# Communications_Board_-_Top.net
KiCad netlist of a schematic drawn in EAGLE
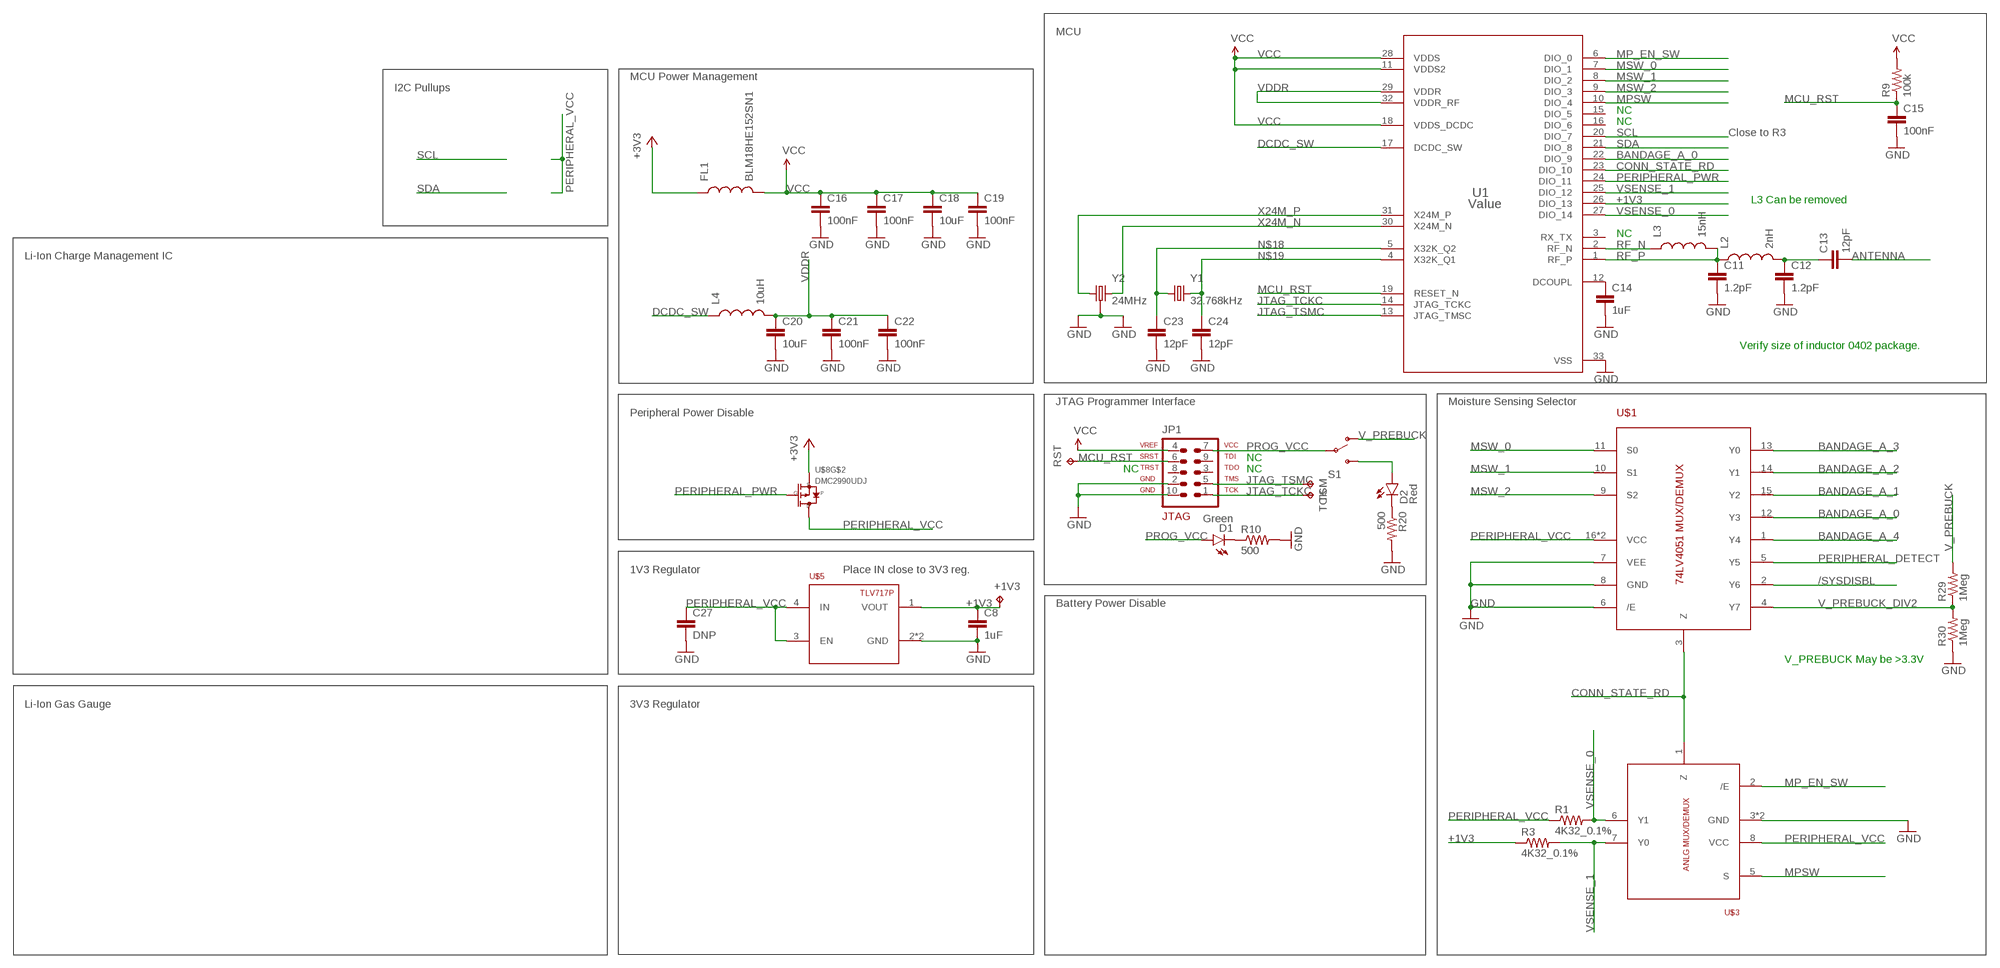
[diagram p0: schematic, sheet 1]
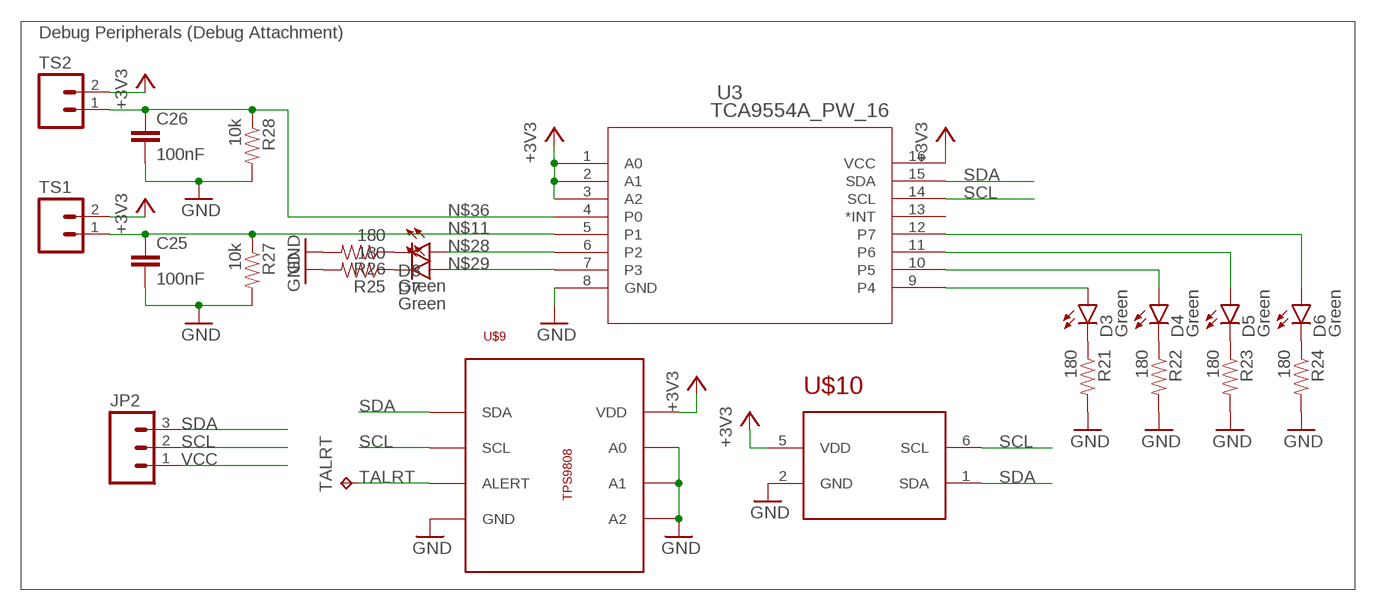
[diagram p1: schematic, sheet 2]
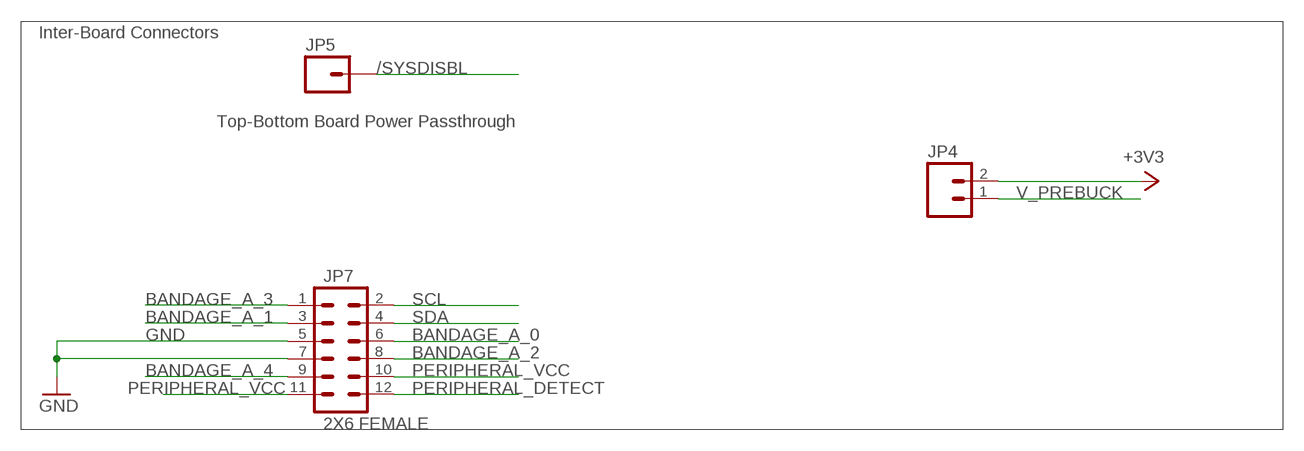
[diagram p2: schematic, sheet 3]

(export (version "E")
  (design (tool "Eeschema 10.0.6"))
  (components
    (comp (ref "+1V3")
      (value "TPTP10R")
      (footprint "eagle-import:TP10R")
      (libsource (lib "eagle-import") (part "TPTP10R"))
    )
    (comp (ref "C8")
      (value "1uF")
      (footprint "eagle-import:0402-CAP")
      (libsource (lib "eagle-import") (part "CAP0402-CAP"))
    )
    (comp (ref "C11")
      (value "1.2pF")
      (footprint "eagle-import:0402-CAP")
      (libsource (lib "eagle-import") (part "CAP0402-CAP"))
    )
    (comp (ref "C12")
      (value "1.2pF")
      (footprint "eagle-import:0402-CAP")
      (libsource (lib "eagle-import") (part "CAP0402-CAP"))
    )
    (comp (ref "C13")
      (value "12pF")
      (footprint "eagle-import:0402-CAP")
      (libsource (lib "eagle-import") (part "CAP0402-CAP"))
    )
    (comp (ref "C14")
      (value "1uF")
      (footprint "eagle-import:0402-CAP")
      (libsource (lib "eagle-import") (part "CAP0402-CAP"))
    )
    (comp (ref "C15")
      (value "100nF")
      (footprint "eagle-import:0402-CAP")
      (libsource (lib "eagle-import") (part "CAP0402-CAP"))
    )
    (comp (ref "C16")
      (value "100nF")
      (footprint "eagle-import:0402-CAP")
      (libsource (lib "eagle-import") (part "CAP0402-CAP"))
    )
    (comp (ref "C17")
      (value "100nF")
      (footprint "eagle-import:0402-CAP")
      (libsource (lib "eagle-import") (part "CAP0402-CAP"))
    )
    (comp (ref "C18")
      (value "10uF")
      (footprint "eagle-import:0402-CAP")
      (libsource (lib "eagle-import") (part "CAP0402-CAP"))
    )
    (comp (ref "C19")
      (value "100nF")
      (footprint "eagle-import:0402-CAP")
      (libsource (lib "eagle-import") (part "CAP0402-CAP"))
    )
    (comp (ref "C20")
      (value "10uF")
      (footprint "eagle-import:0402-CAP")
      (libsource (lib "eagle-import") (part "CAP0402-CAP"))
    )
    (comp (ref "C21")
      (value "100nF")
      (footprint "eagle-import:0402-CAP")
      (libsource (lib "eagle-import") (part "CAP0402-CAP"))
    )
    (comp (ref "C22")
      (value "100nF")
      (footprint "eagle-import:0402-CAP")
      (libsource (lib "eagle-import") (part "CAP0402-CAP"))
    )
    (comp (ref "C23")
      (value "12pF")
      (footprint "eagle-import:0402-CAP")
      (libsource (lib "eagle-import") (part "CAP0402-CAP"))
    )
    (comp (ref "C24")
      (value "12pF")
      (footprint "eagle-import:0402-CAP")
      (libsource (lib "eagle-import") (part "CAP0402-CAP"))
    )
    (comp (ref "C27")
      (value "DNP")
      (footprint "eagle-import:0402-CAP")
      (libsource (lib "eagle-import") (part "CAP0402-CAP"))
    )
    (comp (ref "D1")
      (value "Green")
      (footprint "eagle-import:LED-1206")
      (libsource (lib "eagle-import") (part "LED1206"))
    )
    (comp (ref "D2")
      (value "Red")
      (footprint "eagle-import:LED-1206")
      (libsource (lib "eagle-import") (part "LED1206"))
    )
    (comp (ref "FL1")
      (value "BLM18HE152SN1")
      (footprint "eagle-import:0603")
      (libsource (lib "eagle-import") (part "INDUCTOR0603"))
    )
    (comp (ref "JP1")
      (value "AVR-JTAG-10")
      (footprint "eagle-import:AVR-JTAG-10")
      (libsource (lib "eagle-import") (part "AVR-JTAG-10"))
    )
    (comp (ref "L2")
      (value "2nH")
      (footprint "eagle-import:C0402")
      (libsource (lib "eagle-import") (part "SparkFun-Passives_INDUCTOR0402"))
    )
    (comp (ref "L3")
      (value "15nH")
      (footprint "eagle-import:C0402")
      (libsource (lib "eagle-import") (part "SparkFun-Passives_INDUCTOR0402"))
    )
    (comp (ref "L4")
      (value "10uH")
      (footprint "eagle-import:0603")
      (libsource (lib "eagle-import") (part "INDUCTOR0603"))
    )
    (comp (ref "R1")
      (value "4K32_0.1%")
      (footprint "eagle-import:0402-RES")
      (libsource (lib "eagle-import") (part "RESISTOR0402-RES"))
    )
    (comp (ref "R3")
      (value "4K32_0.1%")
      (footprint "eagle-import:0402-RES")
      (libsource (lib "eagle-import") (part "RESISTOR0402-RES"))
    )
    (comp (ref "R9")
      (value "100k")
      (footprint "eagle-import:0603-RES")
      (libsource (lib "eagle-import") (part "RESISTOR0603-RES"))
    )
    (comp (ref "R10")
      (value "500")
      (footprint "eagle-import:0603-RES")
      (libsource (lib "eagle-import") (part "RESISTOR0603-RES"))
    )
    (comp (ref "R20")
      (value "500")
      (footprint "eagle-import:0603-RES")
      (libsource (lib "eagle-import") (part "RESISTOR0603-RES"))
    )
    (comp (ref "R29")
      (value "1Meg")
      (footprint "eagle-import:0402-RES")
      (libsource (lib "eagle-import") (part "RESISTOR0402-RES"))
    )
    (comp (ref "R30")
      (value "1Meg")
      (footprint "eagle-import:0402-RES")
      (libsource (lib "eagle-import") (part "RESISTOR0402-RES"))
    )
    (comp (ref "RST")
      (value "TPTP10R")
      (footprint "eagle-import:TP10R")
      (libsource (lib "eagle-import") (part "TPTP10R"))
    )
    (comp (ref "S1")
      (value "SWITCH-SPDT")
      (footprint "eagle-import:JS102011SAQN")
      (libsource (lib "eagle-import") (part "SWITCH-SPDT"))
    )
    (comp (ref "TCK")
      (value "TPTP10R")
      (footprint "eagle-import:TP10R")
      (libsource (lib "eagle-import") (part "TPTP10R"))
    )
    (comp (ref "TSM")
      (value "TPTP10R")
      (footprint "eagle-import:TP10R")
      (libsource (lib "eagle-import") (part "TPTP10R"))
    )
    (comp (ref "U$1")
      (value "74LV4051")
      (footprint "eagle-import:SOT763-1")
      (libsource (lib "eagle-import") (part "74LV4051"))
    )
    (comp (ref "U$3")
      (value "74LVC2G53")
      (footprint "eagle-import:SOT833-1")
      (libsource (lib "eagle-import") (part "74LVC2G53"))
    )
    (comp (ref "U$5")
      (value "TLV717P")
      (footprint "eagle-import:X2SON")
      (libsource (lib "eagle-import") (part "TLV717P"))
    )
    (comp (ref "U$8")
      (value "DMC2990UDJ")
      (footprint "eagle-import:SOT963")
      (libsource (lib "eagle-import") (part "DMC2990UDJ"))
    )
    (comp (ref "U1")
      (value "Value")
      (footprint "eagle-import:RHB0032E")
      (fields
        (field (name "ALTERNATEPARTNUMBER") "CC2640F128RHBT")
        (field (name "MANUFACTURER") "Texas Instruments")
        (field (name "PARTNUMBER") "CC2640F128RHBR")
      )
      (libsource (lib "eagle-import") (part "CC2640F128RHBR"))
    )
    (comp (ref "Y1")
      (value "32.768kHz")
      (footprint "eagle-import:CRYSTAL-3.2X1.5")
      (libsource (lib "eagle-import") (part "CRYSTAL"))
    )
    (comp (ref "Y2")
      (value "24MHz")
      (footprint "eagle-import:TSX-3225")
      (libsource (lib "eagle-import") (part "CRYSTAL-GROUNDED"))
    )
    (comp (ref "JP4")
      (value "M021X02_NO_SILK")
      (footprint "eagle-import:1X02_NO_SILK")
      (libsource (lib "eagle-import") (part "M021X02_NO_SILK"))
    )
    (comp (ref "JP5")
      (value "M01PTH")
      (footprint "eagle-import:1X01")
      (libsource (lib "eagle-import") (part "M01PTH"))
    )
    (comp (ref "JP7")
      (value "2X6 FEMALE")
      (footprint "eagle-import:2X6")
      (libsource (lib "eagle-import") (part "M06X2PTH_FEMALE"))
    )
    (comp (ref "C25")
      (value "100nF")
      (footprint "eagle-import:0402-CAP")
      (libsource (lib "eagle-import") (part "CAP0402-CAP"))
    )
    (comp (ref "C26")
      (value "100nF")
      (footprint "eagle-import:0402-CAP")
      (libsource (lib "eagle-import") (part "CAP0402-CAP"))
    )
    (comp (ref "D3")
      (value "Green")
      (footprint "eagle-import:LED-1206")
      (libsource (lib "eagle-import") (part "LED1206"))
    )
    (comp (ref "D4")
      (value "Green")
      (footprint "eagle-import:LED-1206")
      (libsource (lib "eagle-import") (part "LED1206"))
    )
    (comp (ref "D5")
      (value "Green")
      (footprint "eagle-import:LED-1206")
      (libsource (lib "eagle-import") (part "LED1206"))
    )
    (comp (ref "D6")
      (value "Green")
      (footprint "eagle-import:LED-1206")
      (libsource (lib "eagle-import") (part "LED1206"))
    )
    (comp (ref "D7")
      (value "Green")
      (footprint "eagle-import:LED-1206")
      (libsource (lib "eagle-import") (part "LED1206"))
    )
    (comp (ref "D8")
      (value "Green")
      (footprint "eagle-import:LED-1206")
      (libsource (lib "eagle-import") (part "LED1206"))
    )
    (comp (ref "JP2")
      (value "M03PTH")
      (footprint "eagle-import:1X03")
      (libsource (lib "eagle-import") (part "M03PTH"))
    )
    (comp (ref "R21")
      (value "180")
      (footprint "eagle-import:0603-RES")
      (libsource (lib "eagle-import") (part "RESISTOR0603-RES"))
    )
    (comp (ref "R22")
      (value "180")
      (footprint "eagle-import:0603-RES")
      (libsource (lib "eagle-import") (part "RESISTOR0603-RES"))
    )
    (comp (ref "R23")
      (value "180")
      (footprint "eagle-import:0603-RES")
      (libsource (lib "eagle-import") (part "RESISTOR0603-RES"))
    )
    (comp (ref "R24")
      (value "180")
      (footprint "eagle-import:0603-RES")
      (libsource (lib "eagle-import") (part "RESISTOR0603-RES"))
    )
    (comp (ref "R25")
      (value "180")
      (footprint "eagle-import:0603-RES")
      (libsource (lib "eagle-import") (part "RESISTOR0603-RES"))
    )
    (comp (ref "R26")
      (value "180")
      (footprint "eagle-import:0603-RES")
      (libsource (lib "eagle-import") (part "RESISTOR0603-RES"))
    )
    (comp (ref "R27")
      (value "10k")
      (footprint "eagle-import:0603-RES")
      (libsource (lib "eagle-import") (part "RESISTOR0603-RES"))
    )
    (comp (ref "R28")
      (value "10k")
      (footprint "eagle-import:0603-RES")
      (libsource (lib "eagle-import") (part "RESISTOR0603-RES"))
    )
    (comp (ref "TALRT")
      (value "TPTP17R")
      (footprint "eagle-import:TP17R")
      (libsource (lib "eagle-import") (part "TPTP17R"))
    )
    (comp (ref "TS1")
      (value "M02PTH")
      (footprint "eagle-import:1X02")
      (libsource (lib "eagle-import") (part "M02PTH"))
    )
    (comp (ref "TS2")
      (value "M02PTH")
      (footprint "eagle-import:1X02")
      (libsource (lib "eagle-import") (part "M02PTH"))
    )
    (comp (ref "U$9")
      (value "MCP9808")
      (footprint "eagle-import:MSOP8")
      (libsource (lib "eagle-import") (part "MCP9808"))
    )
    (comp (ref "U$10")
      (value "HDC1050")
      (footprint "eagle-import:SON-6")
      (libsource (lib "eagle-import") (part "HDC1050"))
    )
    (comp (ref "U3")
      (value "TCA9554A_PW_16")
      (footprint "eagle-import:PW16")
      (fields
        (field (name "GENERIC_PART_NUMBER") "TCA9554A")
        (field (name "MANUFACTURER") "Texas Instruments")
        (field (name "MANUFACTURER_PART_NUMBER") "tca9554a_pw_16")
      )
      (libsource (lib "eagle-import") (part "TCA9554A_PW_16"))
    )
  )
  (nets
    (net (code "1") (name "+1V3") (class "Default")
      (node (ref "+1V3") (pin "TP") (pinfunction "TP_TP") (pintype "input"))
      (node (ref "C8") (pin "1") (pinfunction "1_1") (pintype "passive"))
      (node (ref "R3") (pin "1") (pinfunction "1_1") (pintype "passive"))
      (node (ref "U$5") (pin "1") (pinfunction "VOUT_1") (pintype "bidirectional"))
      (node (ref "U1") (pin "26") (pinfunction "DIO_13_26") (pintype "bidirectional"))
    )
    (net (code "2") (name "+3V3") (class "Default")
      (node (ref "FL1") (pin "1") (pinfunction "1_1") (pintype "passive"))
      (node (ref "JP4") (pin "2") (pinfunction "2_2") (pintype "passive"))
      (node (ref "TS1") (pin "2") (pinfunction "2_2") (pintype "passive"))
      (node (ref "TS2") (pin "2") (pinfunction "2_2") (pintype "passive"))
      (node (ref "U$10") (pin "5") (pinfunction "VDD_5") (pintype "bidirectional"))
      (node (ref "U$8") (pin "4") (pinfunction "S_4") (pintype "passive"))
      (node (ref "U$9") (pin "8") (pinfunction "VDD_8") (pintype "bidirectional"))
      (node (ref "U3") (pin "1") (pinfunction "A0_1") (pintype "input"))
      (node (ref "U3") (pin "16") (pinfunction "VCC_16") (pintype "power_in"))
      (node (ref "U3") (pin "2") (pinfunction "A1_2") (pintype "input"))
      (node (ref "U3") (pin "3") (pinfunction "A2_3") (pintype "input"))
    )
    (net (code "3") (name "ANTENNA") (class "Default")
      (node (ref "C13") (pin "2") (pinfunction "2_2") (pintype "passive"))
    )
    (net (code "4") (name "BANDAGE_A_0") (class "Default")
      (node (ref "JP7") (pin "6") (pinfunction "6_6") (pintype "passive"))
      (node (ref "U$1") (pin "12") (pinfunction "Y3_12") (pintype "bidirectional"))
      (node (ref "U1") (pin "22") (pinfunction "DIO_9_22") (pintype "bidirectional"))
    )
    (net (code "5") (name "BANDAGE_A_1") (class "Default")
      (node (ref "JP7") (pin "3") (pinfunction "3_3") (pintype "passive"))
      (node (ref "U$1") (pin "15") (pinfunction "Y2_15") (pintype "bidirectional"))
    )
    (net (code "6") (name "BANDAGE_A_2") (class "Default")
      (node (ref "JP7") (pin "8") (pinfunction "8_8") (pintype "passive"))
      (node (ref "U$1") (pin "14") (pinfunction "Y1_14") (pintype "bidirectional"))
    )
    (net (code "7") (name "BANDAGE_A_3") (class "Default")
      (node (ref "JP7") (pin "1") (pinfunction "1_1") (pintype "passive"))
      (node (ref "U$1") (pin "13") (pinfunction "Y0_13") (pintype "bidirectional"))
    )
    (net (code "8") (name "BANDAGE_A_4") (class "Default")
      (node (ref "JP7") (pin "9") (pinfunction "9_9") (pintype "passive"))
      (node (ref "U$1") (pin "1") (pinfunction "Y4_1") (pintype "bidirectional"))
    )
    (net (code "9") (name "CONN_STATE_RD") (class "Default")
      (node (ref "U$1") (pin "3") (pinfunction "Z_3") (pintype "bidirectional"))
      (node (ref "U$3") (pin "1") (pinfunction "Z_1") (pintype "bidirectional"))
      (node (ref "U1") (pin "23") (pinfunction "DIO_10_23") (pintype "bidirectional"))
    )
    (net (code "10") (name "DCDC_SW") (class "Default")
      (node (ref "L4") (pin "1") (pinfunction "1_1") (pintype "passive"))
      (node (ref "U1") (pin "17") (pinfunction "DCDC_SW_17") (pintype "power_in"))
    )
    (net (code "11") (name "GND") (class "Default")
      (node (ref "C11") (pin "2") (pinfunction "2_2") (pintype "passive"))
      (node (ref "C12") (pin "2") (pinfunction "2_2") (pintype "passive"))
      (node (ref "C14") (pin "2") (pinfunction "2_2") (pintype "passive"))
      (node (ref "C15") (pin "2") (pinfunction "2_2") (pintype "passive"))
      (node (ref "C16") (pin "2") (pinfunction "2_2") (pintype "passive"))
      (node (ref "C17") (pin "2") (pinfunction "2_2") (pintype "passive"))
      (node (ref "C18") (pin "2") (pinfunction "2_2") (pintype "passive"))
      (node (ref "C19") (pin "2") (pinfunction "2_2") (pintype "passive"))
      (node (ref "C20") (pin "2") (pinfunction "2_2") (pintype "passive"))
      (node (ref "C21") (pin "2") (pinfunction "2_2") (pintype "passive"))
      (node (ref "C22") (pin "2") (pinfunction "2_2") (pintype "passive"))
      (node (ref "C23") (pin "2") (pinfunction "2_2") (pintype "passive"))
      (node (ref "C24") (pin "2") (pinfunction "2_2") (pintype "passive"))
      (node (ref "C25") (pin "2") (pinfunction "2_2") (pintype "passive"))
      (node (ref "C26") (pin "2") (pinfunction "2_2") (pintype "passive"))
      (node (ref "C27") (pin "2") (pinfunction "2_2") (pintype "passive"))
      (node (ref "C8") (pin "2") (pinfunction "2_2") (pintype "passive"))
      (node (ref "JP1") (pin "10") (pinfunction "10_10") (pintype "passive"))
      (node (ref "JP1") (pin "2") (pinfunction "2_2") (pintype "passive"))
      (node (ref "JP7") (pin "5") (pinfunction "5_5") (pintype "passive"))
      (node (ref "JP7") (pin "7") (pinfunction "7_7") (pintype "passive"))
      (node (ref "R10") (pin "2") (pinfunction "2_2") (pintype "passive"))
      (node (ref "R20") (pin "2") (pinfunction "2_2") (pintype "passive"))
      (node (ref "R21") (pin "2") (pinfunction "2_2") (pintype "passive"))
      (node (ref "R22") (pin "2") (pinfunction "2_2") (pintype "passive"))
      (node (ref "R23") (pin "2") (pinfunction "2_2") (pintype "passive"))
      (node (ref "R24") (pin "2") (pinfunction "2_2") (pintype "passive"))
      (node (ref "R25") (pin "2") (pinfunction "2_2") (pintype "passive"))
      (node (ref "R26") (pin "2") (pinfunction "2_2") (pintype "passive"))
      (node (ref "R27") (pin "2") (pinfunction "2_2") (pintype "passive"))
      (node (ref "R28") (pin "2") (pinfunction "2_2") (pintype "passive"))
      (node (ref "R30") (pin "1") (pinfunction "1_1") (pintype "passive"))
      (node (ref "U$1") (pin "6") (pinfunction "/E_6") (pintype "bidirectional"))
      (node (ref "U$1") (pin "7") (pinfunction "VEE_7") (pintype "bidirectional"))
      (node (ref "U$1") (pin "8") (pinfunction "GND_8") (pintype "bidirectional"))
      (node (ref "U$10") (pin "2") (pinfunction "GND_2") (pintype "bidirectional"))
      (node (ref "U$3") (pin "3") (pinfunction "GND_3") (pintype "bidirectional"))
      (node (ref "U$3") (pin "4") (pinfunction "GND_4") (pintype "bidirectional"))
      (node (ref "U$5") (pin "2") (pinfunction "GND_2") (pintype "bidirectional"))
      (node (ref "U$5") (pin "PAD") (pinfunction "GND_PAD") (pintype "bidirectional"))
      (node (ref "U$9") (pin "4") (pinfunction "GND_4") (pintype "bidirectional"))
      (node (ref "U$9") (pin "5") (pinfunction "A2_5") (pintype "bidirectional"))
      (node (ref "U$9") (pin "6") (pinfunction "A1_6") (pintype "bidirectional"))
      (node (ref "U$9") (pin "7") (pinfunction "A0_7") (pintype "bidirectional"))
      (node (ref "U1") (pin "33") (pinfunction "VSS_33") (pintype "power_in"))
      (node (ref "U3") (pin "8") (pinfunction "GND_8") (pintype "power_in"))
      (node (ref "Y2") (pin "2") (pinfunction "3_2") (pintype "passive"))
      (node (ref "Y2") (pin "4") (pinfunction "3_4") (pintype "passive"))
    )
    (net (code "12") (name "JTAG_TCKC") (class "Default")
      (node (ref "JP1") (pin "1") (pinfunction "1_1") (pintype "passive"))
      (node (ref "TCK") (pin "TP") (pinfunction "TP_TP") (pintype "input"))
      (node (ref "U1") (pin "14") (pinfunction "JTAG_TCKC_14") (pintype "bidirectional"))
    )
    (net (code "13") (name "JTAG_TSMC") (class "Default")
      (node (ref "JP1") (pin "5") (pinfunction "5_5") (pintype "passive"))
      (node (ref "TSM") (pin "TP") (pinfunction "TP_TP") (pintype "input"))
      (node (ref "U1") (pin "13") (pinfunction "JTAG_TMSC_13") (pintype "bidirectional"))
    )
    (net (code "14") (name "MCU_RST") (class "Default")
      (node (ref "C15") (pin "1") (pinfunction "1_1") (pintype "passive"))
      (node (ref "JP1") (pin "6") (pinfunction "6_6") (pintype "passive"))
      (node (ref "R9") (pin "1") (pinfunction "1_1") (pintype "passive"))
      (node (ref "RST") (pin "TP") (pinfunction "TP_TP") (pintype "input"))
      (node (ref "U1") (pin "19") (pinfunction "RESET_N_19") (pintype "input"))
    )
    (net (code "15") (name "MPSW") (class "Default")
      (node (ref "U$3") (pin "5") (pinfunction "S_5") (pintype "bidirectional"))
      (node (ref "U1") (pin "10") (pinfunction "DIO_4_10") (pintype "bidirectional"))
    )
    (net (code "16") (name "MP_EN_SW") (class "Default")
      (node (ref "U$3") (pin "2") (pinfunction "/E_2") (pintype "bidirectional"))
      (node (ref "U1") (pin "6") (pinfunction "DIO_0_6") (pintype "bidirectional"))
    )
    (net (code "17") (name "MSW_0") (class "Default")
      (node (ref "U$1") (pin "11") (pinfunction "S0_11") (pintype "bidirectional"))
      (node (ref "U1") (pin "7") (pinfunction "DIO_1_7") (pintype "bidirectional"))
    )
    (net (code "18") (name "MSW_1") (class "Default")
      (node (ref "U$1") (pin "10") (pinfunction "S1_10") (pintype "bidirectional"))
      (node (ref "U1") (pin "8") (pinfunction "DIO_2_8") (pintype "bidirectional"))
    )
    (net (code "19") (name "MSW_2") (class "Default")
      (node (ref "U$1") (pin "9") (pinfunction "S2_9") (pintype "bidirectional"))
      (node (ref "U1") (pin "9") (pinfunction "DIO_3_9") (pintype "bidirectional"))
    )
    (net (code "20") (name "N$11") (class "Default")
      (node (ref "C25") (pin "1") (pinfunction "1_1") (pintype "passive"))
      (node (ref "R27") (pin "1") (pinfunction "1_1") (pintype "passive"))
      (node (ref "TS1") (pin "1") (pinfunction "1_1") (pintype "passive"))
      (node (ref "U3") (pin "5") (pinfunction "P1_5") (pintype "bidirectional"))
    )
    (net (code "21") (name "N$18") (class "Default")
      (node (ref "C23") (pin "1") (pinfunction "1_1") (pintype "passive"))
      (node (ref "U1") (pin "5") (pinfunction "X32K_Q2_5") (pintype "bidirectional"))
      (node (ref "Y1") (pin "1") (pinfunction "1_1") (pintype "passive"))
    )
    (net (code "22") (name "N$19") (class "Default")
      (node (ref "C24") (pin "1") (pinfunction "1_1") (pintype "passive"))
      (node (ref "U1") (pin "4") (pinfunction "X32K_Q1_4") (pintype "bidirectional"))
      (node (ref "Y1") (pin "2") (pinfunction "2_2") (pintype "passive"))
    )
    (net (code "23") (name "N$28") (class "Default")
      (node (ref "D8") (pin "A") (pinfunction "A_A") (pintype "passive"))
      (node (ref "U3") (pin "6") (pinfunction "P2_6") (pintype "bidirectional"))
    )
    (net (code "24") (name "N$29") (class "Default")
      (node (ref "D7") (pin "A") (pinfunction "A_A") (pintype "passive"))
      (node (ref "U3") (pin "7") (pinfunction "P3_7") (pintype "bidirectional"))
    )
    (net (code "25") (name "N$36") (class "Default")
      (node (ref "C26") (pin "1") (pinfunction "1_1") (pintype "passive"))
      (node (ref "R28") (pin "1") (pinfunction "1_1") (pintype "passive"))
      (node (ref "TS2") (pin "1") (pinfunction "1_1") (pintype "passive"))
      (node (ref "U3") (pin "4") (pinfunction "P0_4") (pintype "bidirectional"))
    )
    (net (code "26") (name "Net-(C12-Pad1)") (class "Default")
      (node (ref "C12") (pin "1") (pinfunction "1_1") (pintype "passive"))
      (node (ref "C13") (pin "1") (pinfunction "1_1") (pintype "passive"))
      (node (ref "L2") (pin "2") (pinfunction "2_2") (pintype "passive"))
    )
    (net (code "27") (name "Net-(D1-PadC)") (class "Default")
      (node (ref "D1") (pin "C") (pinfunction "C_C") (pintype "passive"))
      (node (ref "R10") (pin "1") (pinfunction "1_1") (pintype "passive"))
    )
    (net (code "28") (name "Net-(D2-PadC)") (class "Default")
      (node (ref "D2") (pin "C") (pinfunction "C_C") (pintype "passive"))
      (node (ref "R20") (pin "1") (pinfunction "1_1") (pintype "passive"))
    )
    (net (code "29") (name "Net-(D3-PadC)") (class "Default")
      (node (ref "D3") (pin "C") (pinfunction "C_C") (pintype "passive"))
      (node (ref "R21") (pin "1") (pinfunction "1_1") (pintype "passive"))
    )
    (net (code "30") (name "Net-(D4-PadC)") (class "Default")
      (node (ref "D4") (pin "C") (pinfunction "C_C") (pintype "passive"))
      (node (ref "R22") (pin "1") (pinfunction "1_1") (pintype "passive"))
    )
    (net (code "31") (name "Net-(D5-PadC)") (class "Default")
      (node (ref "D5") (pin "C") (pinfunction "C_C") (pintype "passive"))
      (node (ref "R23") (pin "1") (pinfunction "1_1") (pintype "passive"))
    )
    (net (code "32") (name "Net-(D6-PadC)") (class "Default")
      (node (ref "D6") (pin "C") (pinfunction "C_C") (pintype "passive"))
      (node (ref "R24") (pin "1") (pinfunction "1_1") (pintype "passive"))
    )
    (net (code "33") (name "Net-(D7-PadC)") (class "Default")
      (node (ref "D7") (pin "C") (pinfunction "C_C") (pintype "passive"))
      (node (ref "R25") (pin "1") (pinfunction "1_1") (pintype "passive"))
    )
    (net (code "34") (name "Net-(D8-PadC)") (class "Default")
      (node (ref "D8") (pin "C") (pinfunction "C_C") (pintype "passive"))
      (node (ref "R26") (pin "1") (pinfunction "1_1") (pintype "passive"))
    )
    (net (code "35") (name "Net-(S1-S)") (class "Default")
      (node (ref "D2") (pin "A") (pinfunction "A_A") (pintype "passive"))
      (node (ref "S1") (pin "3") (pinfunction "S_3") (pintype "passive"))
    )
    (net (code "36") (name "Net-(U1-DCOUPL)") (class "Default")
      (node (ref "C14") (pin "1") (pinfunction "1_1") (pintype "passive"))
      (node (ref "U1") (pin "12") (pinfunction "DCOUPL_12") (pintype "power_in"))
    )
    (net (code "37") (name "Net-(U3-P4)") (class "Default")
      (node (ref "D3") (pin "A") (pinfunction "A_A") (pintype "passive"))
      (node (ref "U3") (pin "9") (pinfunction "P4_9") (pintype "bidirectional"))
    )
    (net (code "38") (name "Net-(U3-P5)") (class "Default")
      (node (ref "D4") (pin "A") (pinfunction "A_A") (pintype "passive"))
      (node (ref "U3") (pin "10") (pinfunction "P5_10") (pintype "bidirectional"))
    )
    (net (code "39") (name "Net-(U3-P6)") (class "Default")
      (node (ref "D5") (pin "A") (pinfunction "A_A") (pintype "passive"))
      (node (ref "U3") (pin "11") (pinfunction "P6_11") (pintype "bidirectional"))
    )
    (net (code "40") (name "Net-(U3-P7)") (class "Default")
      (node (ref "D6") (pin "A") (pinfunction "A_A") (pintype "passive"))
      (node (ref "U3") (pin "12") (pinfunction "P7_12") (pintype "bidirectional"))
    )
    (net (code "41") (name "PERIPHERAL_DETECT") (class "Default")
      (node (ref "JP7") (pin "12") (pinfunction "12_12") (pintype "passive"))
      (node (ref "U$1") (pin "5") (pinfunction "Y5_5") (pintype "bidirectional"))
    )
    (net (code "42") (name "PERIPHERAL_PWR") (class "Default")
      (node (ref "U$8") (pin "5") (pinfunction "G_5") (pintype "passive"))
      (node (ref "U1") (pin "24") (pinfunction "DIO_11_24") (pintype "bidirectional"))
    )
    (net (code "43") (name "PERIPHERAL_VCC") (class "Default")
      (node (ref "C27") (pin "1") (pinfunction "1_1") (pintype "passive"))
      (node (ref "JP7") (pin "10") (pinfunction "10_10") (pintype "passive"))
      (node (ref "JP7") (pin "11") (pinfunction "11_11") (pintype "passive"))
      (node (ref "R1") (pin "1") (pinfunction "1_1") (pintype "passive"))
      (node (ref "U$1") (pin "16") (pinfunction "VCC_16") (pintype "bidirectional"))
      (node (ref "U$1") (pin "PAD") (pinfunction "VCC_PAD") (pintype "bidirectional"))
      (node (ref "U$3") (pin "8") (pinfunction "VCC_8") (pintype "bidirectional"))
      (node (ref "U$5") (pin "3") (pinfunction "EN_3") (pintype "bidirectional"))
      (node (ref "U$5") (pin "4") (pinfunction "IN_4") (pintype "bidirectional"))
      (node (ref "U$8") (pin "3") (pinfunction "D_3") (pintype "passive"))
    )
    (net (code "44") (name "PROG_VCC") (class "Default")
      (node (ref "D1") (pin "A") (pinfunction "A_A") (pintype "passive"))
      (node (ref "JP1") (pin "7") (pinfunction "7_7") (pintype "passive"))
      (node (ref "S1") (pin "2") (pinfunction "P_2") (pintype "passive"))
    )
    (net (code "45") (name "RF_N") (class "Default")
      (node (ref "L3") (pin "1") (pinfunction "1_1") (pintype "passive"))
      (node (ref "U1") (pin "2") (pinfunction "RF_N_2") (pintype "bidirectional"))
    )
    (net (code "46") (name "RF_P") (class "Default")
      (node (ref "C11") (pin "1") (pinfunction "1_1") (pintype "passive"))
      (node (ref "L2") (pin "1") (pinfunction "1_1") (pintype "passive"))
      (node (ref "L3") (pin "2") (pinfunction "2_2") (pintype "passive"))
      (node (ref "U1") (pin "1") (pinfunction "RF_P_1") (pintype "bidirectional"))
    )
    (net (code "47") (name "SCL") (class "Default")
      (node (ref "JP2") (pin "2") (pinfunction "2_2") (pintype "passive"))
      (node (ref "JP7") (pin "2") (pinfunction "2_2") (pintype "passive"))
      (node (ref "U$10") (pin "6") (pinfunction "SCL_6") (pintype "bidirectional"))
      (node (ref "U$9") (pin "2") (pinfunction "SCL_2") (pintype "bidirectional"))
      (node (ref "U1") (pin "20") (pinfunction "DIO_7_20") (pintype "bidirectional"))
      (node (ref "U3") (pin "14") (pinfunction "SCL_14") (pintype "bidirectional"))
    )
    (net (code "48") (name "SDA") (class "Default")
      (node (ref "JP2") (pin "3") (pinfunction "3_3") (pintype "passive"))
      (node (ref "JP7") (pin "4") (pinfunction "4_4") (pintype "passive"))
      (node (ref "U$10") (pin "1") (pinfunction "SDA_1") (pintype "bidirectional"))
      (node (ref "U$9") (pin "1") (pinfunction "SDA_1") (pintype "bidirectional"))
      (node (ref "U1") (pin "21") (pinfunction "DIO_8_21") (pintype "bidirectional"))
      (node (ref "U3") (pin "15") (pinfunction "SDA_15") (pintype "bidirectional"))
    )
    (net (code "49") (name "TALRT") (class "Default")
      (node (ref "TALRT") (pin "TP") (pinfunction "TP_TP") (pintype "input"))
      (node (ref "U$9") (pin "3") (pinfunction "ALERT_3") (pintype "bidirectional"))
    )
    (net (code "50") (name "VCC") (class "Default")
      (node (ref "C16") (pin "1") (pinfunction "1_1") (pintype "passive"))
      (node (ref "C17") (pin "1") (pinfunction "1_1") (pintype "passive"))
      (node (ref "C18") (pin "1") (pinfunction "1_1") (pintype "passive"))
      (node (ref "C19") (pin "1") (pinfunction "1_1") (pintype "passive"))
      (node (ref "FL1") (pin "2") (pinfunction "2_2") (pintype "passive"))
      (node (ref "JP1") (pin "4") (pinfunction "4_4") (pintype "passive"))
      (node (ref "JP2") (pin "1") (pinfunction "1_1") (pintype "passive"))
      (node (ref "R9") (pin "2") (pinfunction "2_2") (pintype "passive"))
      (node (ref "U1") (pin "11") (pinfunction "VDDS2_11") (pintype "power_in"))
      (node (ref "U1") (pin "18") (pinfunction "VDDS_DCDC_18") (pintype "power_in"))
      (node (ref "U1") (pin "28") (pinfunction "VDDS_28") (pintype "power_in"))
    )
    (net (code "51") (name "VDDR") (class "Default")
      (node (ref "C20") (pin "1") (pinfunction "1_1") (pintype "passive"))
      (node (ref "C21") (pin "1") (pinfunction "1_1") (pintype "passive"))
      (node (ref "C22") (pin "1") (pinfunction "1_1") (pintype "passive"))
      (node (ref "L4") (pin "2") (pinfunction "2_2") (pintype "passive"))
      (node (ref "U1") (pin "29") (pinfunction "VDDR_29") (pintype "power_in"))
      (node (ref "U1") (pin "32") (pinfunction "VDDR_RF_32") (pintype "power_in"))
    )
    (net (code "52") (name "VSENSE_0") (class "Default")
      (node (ref "R1") (pin "2") (pinfunction "2_2") (pintype "passive"))
      (node (ref "U$3") (pin "6") (pinfunction "Y1_6") (pintype "bidirectional"))
      (node (ref "U1") (pin "27") (pinfunction "DIO_14_27") (pintype "bidirectional"))
    )
    (net (code "53") (name "VSENSE_1") (class "Default")
      (node (ref "R3") (pin "2") (pinfunction "2_2") (pintype "passive"))
      (node (ref "U$3") (pin "7") (pinfunction "Y0_7") (pintype "bidirectional"))
      (node (ref "U1") (pin "25") (pinfunction "DIO_12_25") (pintype "bidirectional"))
    )
    (net (code "54") (name "V_PREBUCK") (class "Default")
      (node (ref "JP4") (pin "1") (pinfunction "1_1") (pintype "passive"))
      (node (ref "R29") (pin "2") (pinfunction "2_2") (pintype "passive"))
      (node (ref "S1") (pin "1") (pinfunction "O_1") (pintype "passive"))
    )
    (net (code "55") (name "V_PREBUCK_DIV2") (class "Default")
      (node (ref "R29") (pin "1") (pinfunction "1_1") (pintype "passive"))
      (node (ref "R30") (pin "2") (pinfunction "2_2") (pintype "passive"))
      (node (ref "U$1") (pin "4") (pinfunction "Y7_4") (pintype "bidirectional"))
    )
    (net (code "56") (name "X24M_N") (class "Default")
      (node (ref "U1") (pin "30") (pinfunction "X24M_N_30") (pintype "bidirectional"))
      (node (ref "Y2") (pin "3") (pinfunction "2_3") (pintype "passive"))
    )
    (net (code "57") (name "X24M_P") (class "Default")
      (node (ref "U1") (pin "31") (pinfunction "X24M_P_31") (pintype "bidirectional"))
      (node (ref "Y2") (pin "1") (pinfunction "1_1") (pintype "passive"))
    )
    (net (code "58") (name "unconnected-(JP1-Pad3)") (class "Default")
      (node (ref "JP1") (pin "3") (pinfunction "3_3") (pintype "passive"))
    )
    (net (code "59") (name "unconnected-(JP1-Pad8)") (class "Default")
      (node (ref "JP1") (pin "8") (pinfunction "8_8") (pintype "passive"))
    )
    (net (code "60") (name "unconnected-(JP1-Pad9)") (class "Default")
      (node (ref "JP1") (pin "9") (pinfunction "9_9") (pintype "passive"))
    )
    (net (code "61") (name "unconnected-(U1-DIO_5-Pad15)") (class "Default")
      (node (ref "U1") (pin "15") (pinfunction "DIO_5_15") (pintype "bidirectional"))
    )
    (net (code "62") (name "unconnected-(U1-DIO_6-Pad16)") (class "Default")
      (node (ref "U1") (pin "16") (pinfunction "DIO_6_16") (pintype "bidirectional"))
    )
    (net (code "63") (name "unconnected-(U1-RX_TX-Pad3)") (class "Default")
      (node (ref "U1") (pin "3") (pinfunction "RX_TX_3") (pintype "bidirectional"))
    )
    (net (code "64") (name "unconnected-(U3-*INT-Pad13)") (class "Default")
      (node (ref "U3") (pin "13") (pinfunction "*INT_13") (pintype "output"))
    )
    (net (code "65") (name "{slash}SYSDISBL") (class "Default")
      (node (ref "JP5") (pin "1") (pinfunction "1_1") (pintype "passive"))
      (node (ref "U$1") (pin "2") (pinfunction "Y6_2") (pintype "bidirectional"))
    )
  )
)
